# Amp.net
KiCad netlist of a schematic drawn in Altium Designer
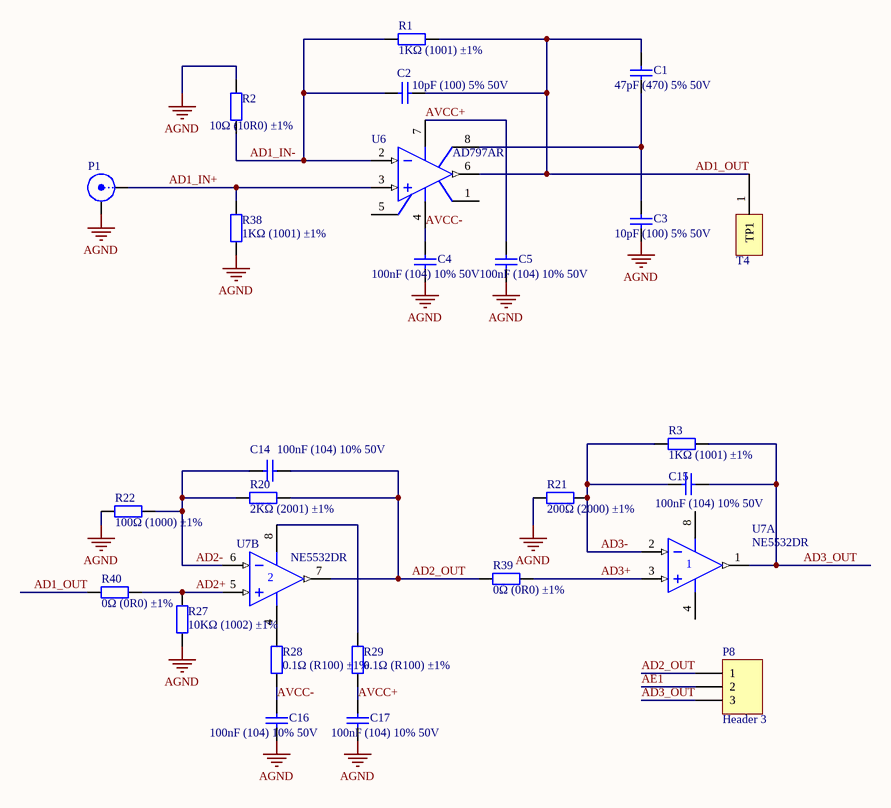
[diagram p0: Amp.SchDoc]

(export (version "E")
  (design (tool "Eeschema 10.0.6"))
  (components
    (comp (ref "C1")
      (value "47pF (470) 5% 50V")
      (footprint "0603_C")
      (description "贴片电容")
      (libsource (lib "Miscellaneous Devices LC") (part "0603 47pF (470) 5% 50V"))
    )
    (comp (ref "C2")
      (value "10pF (100) 5% 50V")
      (footprint "0603_C")
      (description "贴片电容")
      (libsource (lib "Miscellaneous Devices LC") (part "0603 10pF (100) 5% 50V"))
    )
    (comp (ref "C3")
      (value "10pF (100) 5% 50V")
      (footprint "0603_C")
      (description "贴片电容")
      (libsource (lib "Miscellaneous Devices LC") (part "0603 10pF (100) 5% 50V"))
    )
    (comp (ref "C4")
      (value "100nF (104) 10% 50V")
      (footprint "0603_C")
      (description "贴片电容")
      (libsource (lib "Miscellaneous Devices LC") (part "0603 100nF (104) 10% 50V"))
    )
    (comp (ref "C5")
      (value "100nF (104) 10% 50V")
      (footprint "0603_C")
      (description "贴片电容")
      (libsource (lib "Miscellaneous Devices LC") (part "0603 100nF (104) 10% 50V"))
    )
    (comp (ref "C14")
      (value "100nF (104) 10% 50V")
      (footprint "0603_C")
      (description "贴片电容")
      (libsource (lib "Miscellaneous Devices LC") (part "0603 100nF (104) 10% 50V"))
    )
    (comp (ref "C15")
      (value "100nF (104) 10% 50V")
      (footprint "0603_C")
      (description "贴片电容")
      (libsource (lib "Miscellaneous Devices LC") (part "0603 100nF (104) 10% 50V"))
    )
    (comp (ref "C16")
      (value "100nF (104) 10% 50V")
      (footprint "0603_C")
      (description "贴片电容")
      (libsource (lib "Miscellaneous Devices LC") (part "0603 100nF (104) 10% 50V"))
    )
    (comp (ref "C17")
      (value "100nF (104) 10% 50V")
      (footprint "0603_C")
      (description "贴片电容")
      (libsource (lib "Miscellaneous Devices LC") (part "0603 100nF (104) 10% 50V"))
    )
    (comp (ref "P1")
      (value "SMB")
      (footprint "SMB_V-RJ45")
      (description "SMB Straight Connector")
      (fields (field (name "PUBLISHER") "Altium Limited"))
      (libsource (lib "Miscellaneous Connectors") (part "SMB"))
    )
    (comp (ref "P8")
      (value "Header 3")
      (footprint "HDR1X3")
      (description "Header, 3-Pin")
      (fields (field (name "PUBLISHER") "Altium Limited"))
      (libsource (lib "Miscellaneous Connectors") (part "Header 3"))
    )
    (comp (ref "R1")
      (value "1KΩ (1001) ±1%")
      (footprint "0603_R")
      (description "贴片电阻")
      (libsource (lib "") (part "0603 1KΩ (1001) 1%_2"))
    )
    (comp (ref "R2")
      (value "10Ω (10R0) ±1%")
      (footprint "0603_R")
      (description "贴片电阻")
      (libsource (lib "Miscellaneous Devices LC") (part "0603 10Ω (10R0) 1%"))
    )
    (comp (ref "R3")
      (value "1KΩ (1001) ±1%")
      (footprint "0603_R")
      (description "贴片电阻")
      (libsource (lib "") (part "0603 1KΩ (1001) 1%_1"))
    )
    (comp (ref "R20")
      (value "2KΩ (2001) ±1%")
      (footprint "0603_R")
      (description "贴片电阻")
      (libsource (lib "Miscellaneous Devices LC") (part "0603 2KΩ (2001) 1%"))
    )
    (comp (ref "R21")
      (value "200Ω (2000) ±1%")
      (footprint "0603_R")
      (description "贴片电阻")
      (libsource (lib "Miscellaneous Devices LC") (part "0603 200Ω (2000) 1%"))
    )
    (comp (ref "R22")
      (value "100Ω (1000) ±1%")
      (footprint "0603_R")
      (description "贴片电阻")
      (libsource (lib "Miscellaneous Devices LC") (part "0603 100Ω (1000) 1%"))
    )
    (comp (ref "R27")
      (value "10KΩ (1002) ±1%")
      (footprint "0603_R")
      (description "贴片电阻")
      (libsource (lib "Miscellaneous Devices LC") (part "0603 10KΩ (1002) 1%"))
    )
    (comp (ref "R28")
      (value "0.1Ω (R100) ±1%")
      (footprint "1206_R")
      (description "贴片电阻")
      (libsource (lib "Miscellaneous Devices LC") (part "1206 0.1Ω (R100) 1%"))
    )
    (comp (ref "R29")
      (value "0.1Ω (R100) ±1%")
      (footprint "1206_R")
      (description "贴片电阻")
      (libsource (lib "Miscellaneous Devices LC") (part "1206 0.1Ω (R100) 1%"))
    )
    (comp (ref "R38")
      (value "1KΩ (1001) ±1%")
      (footprint "0603_R")
      (description "贴片电阻")
      (libsource (lib "Miscellaneous Devices LC") (part "0603 1KΩ (1001) 1%"))
    )
    (comp (ref "R39")
      (value "0Ω (0R0) ±1%")
      (footprint "0603_R")
      (description "贴片电阻")
      (libsource (lib "Miscellaneous Devices LC") (part "0603 0Ω (0R0) 1%"))
    )
    (comp (ref "R40")
      (value "0Ω (0R0) ±1%")
      (footprint "0603_R")
      (description "贴片电阻")
      (libsource (lib "Miscellaneous Devices LC") (part "0603 0Ω (0R0) 1%"))
    )
    (comp (ref "T4") (value "TP1") (footprint "TP1") (libsource (lib "CHK-I") (part "TP1")))
    (comp (ref "U6")
      (value "AD797AR")
      (footprint "SO-8C_N")
      (description "Ultra-Low Distortion, Ultra-Low Noise Operational Amplifier")
      (fields (field (name "PUBLISHER") "Altium Limited"))
      (libsource (lib "AD Operational Amplifier") (part "AD797AR"))
    )
    (comp (ref "U7")
      (value "NE5532DR")
      (footprint "SOIC-8_150mil")
      (description "功放")
      (libsource (lib "Miscellaneous Devices LC") (part "NE5532DR_[C7426]"))
    )
  )
  (nets
    (net (code "1") (name "/AD1_IN+") (class "Default")
      (node (ref "P1") (pin "1") (pinfunction "X_1") (pintype "passive"))
      (node (ref "R38") (pin "2") (pinfunction "2_2") (pintype "passive"))
      (node (ref "U6") (pin "3") (pinfunction "IN+_3") (pintype "input"))
    )
    (net (code "2") (name "/AD1_IN-") (class "Default")
      (node (ref "C2") (pin "2") (pinfunction "2_2") (pintype "passive"))
      (node (ref "R1") (pin "2") (pinfunction "2_2") (pintype "passive"))
      (node (ref "R2") (pin "1") (pinfunction "1_1") (pintype "passive"))
      (node (ref "U6") (pin "2") (pinfunction "IN-_2") (pintype "input"))
    )
    (net (code "3") (name "/AD1_OUT") (class "Default")
      (node (ref "C1") (pin "2") (pinfunction "2_2") (pintype "passive"))
      (node (ref "C2") (pin "1") (pinfunction "1_1") (pintype "passive"))
      (node (ref "R1") (pin "1") (pinfunction "1_1") (pintype "passive"))
      (node (ref "R40") (pin "1") (pinfunction "1_1") (pintype "passive"))
      (node (ref "T4") (pin "1") (pinfunction "TP1_1") (pintype "passive"))
      (node (ref "U6") (pin "6") (pinfunction "OUT_6") (pintype "output"))
    )
    (net (code "4") (name "/AD2+") (class "Default")
      (node (ref "R27") (pin "2") (pinfunction "2_2") (pintype "passive"))
      (node (ref "R40") (pin "2") (pinfunction "2_2") (pintype "passive"))
      (node (ref "U7") (pin "5") (pinfunction "IN+_5") (pintype "input"))
    )
    (net (code "5") (name "/AD2-") (class "Default")
      (node (ref "C14") (pin "1") (pinfunction "1_1") (pintype "passive"))
      (node (ref "R20") (pin "1") (pinfunction "1_1") (pintype "passive"))
      (node (ref "R22") (pin "2") (pinfunction "2_2") (pintype "passive"))
      (node (ref "U7") (pin "6") (pinfunction "IN-_6") (pintype "input"))
    )
    (net (code "6") (name "/AD2_OUT") (class "Default")
      (node (ref "C14") (pin "2") (pinfunction "2_2") (pintype "passive"))
      (node (ref "P8") (pin "1") (pinfunction "1_1") (pintype "passive"))
      (node (ref "R20") (pin "2") (pinfunction "2_2") (pintype "passive"))
      (node (ref "R39") (pin "1") (pinfunction "1_1") (pintype "passive"))
      (node (ref "U7") (pin "7") (pinfunction "OUT_7") (pintype "output"))
    )
    (net (code "7") (name "/AD3+") (class "Default")
      (node (ref "R39") (pin "2") (pinfunction "2_2") (pintype "passive"))
      (node (ref "U7") (pin "3") (pinfunction "IN+_3") (pintype "input"))
    )
    (net (code "8") (name "/AD3-") (class "Default")
      (node (ref "C15") (pin "1") (pinfunction "1_1") (pintype "passive"))
      (node (ref "R21") (pin "2") (pinfunction "2_2") (pintype "passive"))
      (node (ref "R3") (pin "1") (pinfunction "1_1") (pintype "passive"))
      (node (ref "U7") (pin "2") (pinfunction "IN-_2") (pintype "input"))
    )
    (net (code "9") (name "/AD3_OUT") (class "Default")
      (node (ref "C15") (pin "2") (pinfunction "2_2") (pintype "passive"))
      (node (ref "P8") (pin "3") (pinfunction "3_3") (pintype "passive"))
      (node (ref "R3") (pin "2") (pinfunction "2_2") (pintype "passive"))
      (node (ref "U7") (pin "1") (pinfunction "OUT_1") (pintype "output"))
    )
    (net (code "10") (name "/AE1") (class "Default")
      (node (ref "P8") (pin "2") (pinfunction "2_2") (pintype "passive"))
    )
    (net (code "11") (name "/AVCC+") (class "Default")
      (node (ref "C17") (pin "2") (pinfunction "2_2") (pintype "passive"))
      (node (ref "C5") (pin "2") (pinfunction "2_2") (pintype "passive"))
      (node (ref "R29") (pin "1") (pinfunction "1_1") (pintype "passive"))
      (node (ref "U6") (pin "7") (pinfunction "V+_7") (pintype "power_in"))
    )
    (net (code "12") (name "/AVCC-") (class "Default")
      (node (ref "C16") (pin "2") (pinfunction "2_2") (pintype "passive"))
      (node (ref "C4") (pin "2") (pinfunction "2_2") (pintype "passive"))
      (node (ref "R28") (pin "1") (pinfunction "1_1") (pintype "passive"))
      (node (ref "U6") (pin "4") (pinfunction "V-_4") (pintype "power_in"))
    )
    (net (code "13") (name "AGND") (class "Default")
      (node (ref "C16") (pin "1") (pinfunction "1_1") (pintype "passive"))
      (node (ref "C17") (pin "1") (pinfunction "1_1") (pintype "passive"))
      (node (ref "C3") (pin "1") (pinfunction "1_1") (pintype "passive"))
      (node (ref "C4") (pin "1") (pinfunction "1_1") (pintype "passive"))
      (node (ref "C5") (pin "1") (pinfunction "1_1") (pintype "passive"))
      (node (ref "P1") (pin "2") (pinfunction "Y_2") (pintype "passive"))
      (node (ref "R2") (pin "2") (pinfunction "2_2") (pintype "passive"))
      (node (ref "R21") (pin "1") (pinfunction "1_1") (pintype "passive"))
      (node (ref "R22") (pin "1") (pinfunction "1_1") (pintype "passive"))
      (node (ref "R27") (pin "1") (pinfunction "1_1") (pintype "passive"))
      (node (ref "R38") (pin "1") (pinfunction "1_1") (pintype "passive"))
    )
    (net (code "14") (name "Net-(U6-DECMPEN)") (class "Default")
      (node (ref "C1") (pin "1") (pinfunction "1_1") (pintype "passive"))
      (node (ref "C3") (pin "2") (pinfunction "2_2") (pintype "passive"))
      (node (ref "U6") (pin "8") (pinfunction "DECMPEN_8") (pintype "passive"))
    )
    (net (code "15") (name "Net-(U7B-V+)") (class "Default")
      (node (ref "R29") (pin "2") (pinfunction "2_2") (pintype "passive"))
      (node (ref "U7") (pin "8") (pinfunction "V+_8") (pintype "power_in"))
    )
    (net (code "16") (name "Net-(U7B-V-)") (class "Default")
      (node (ref "R28") (pin "2") (pinfunction "2_2") (pintype "passive"))
      (node (ref "U7") (pin "4") (pinfunction "V-_4") (pintype "power_in"))
    )
    (net (code "17") (name "unconnected-(U6-OS_NUL-Pad1)") (class "Default")
      (node (ref "U6") (pin "1") (pinfunction "OS_NUL_1") (pintype "passive"))
    )
    (net (code "18") (name "unconnected-(U6-OS_NUL-Pad5)") (class "Default")
      (node (ref "U6") (pin "5") (pinfunction "OS_NUL_5") (pintype "passive"))
    )
    (net (code "19") (name "unconnected-(U7A-V+-Pad8)") (class "Default")
      (node (ref "U7") (pin "8") (pinfunction "V+_8") (pintype "power_in"))
    )
    (net (code "20") (name "unconnected-(U7A-V--Pad4)") (class "Default")
      (node (ref "U7") (pin "4") (pinfunction "V-_4") (pintype "power_in"))
    )
  )
)
